# CapBank.net
KiCad netlist of a schematic drawn in Altium Designer
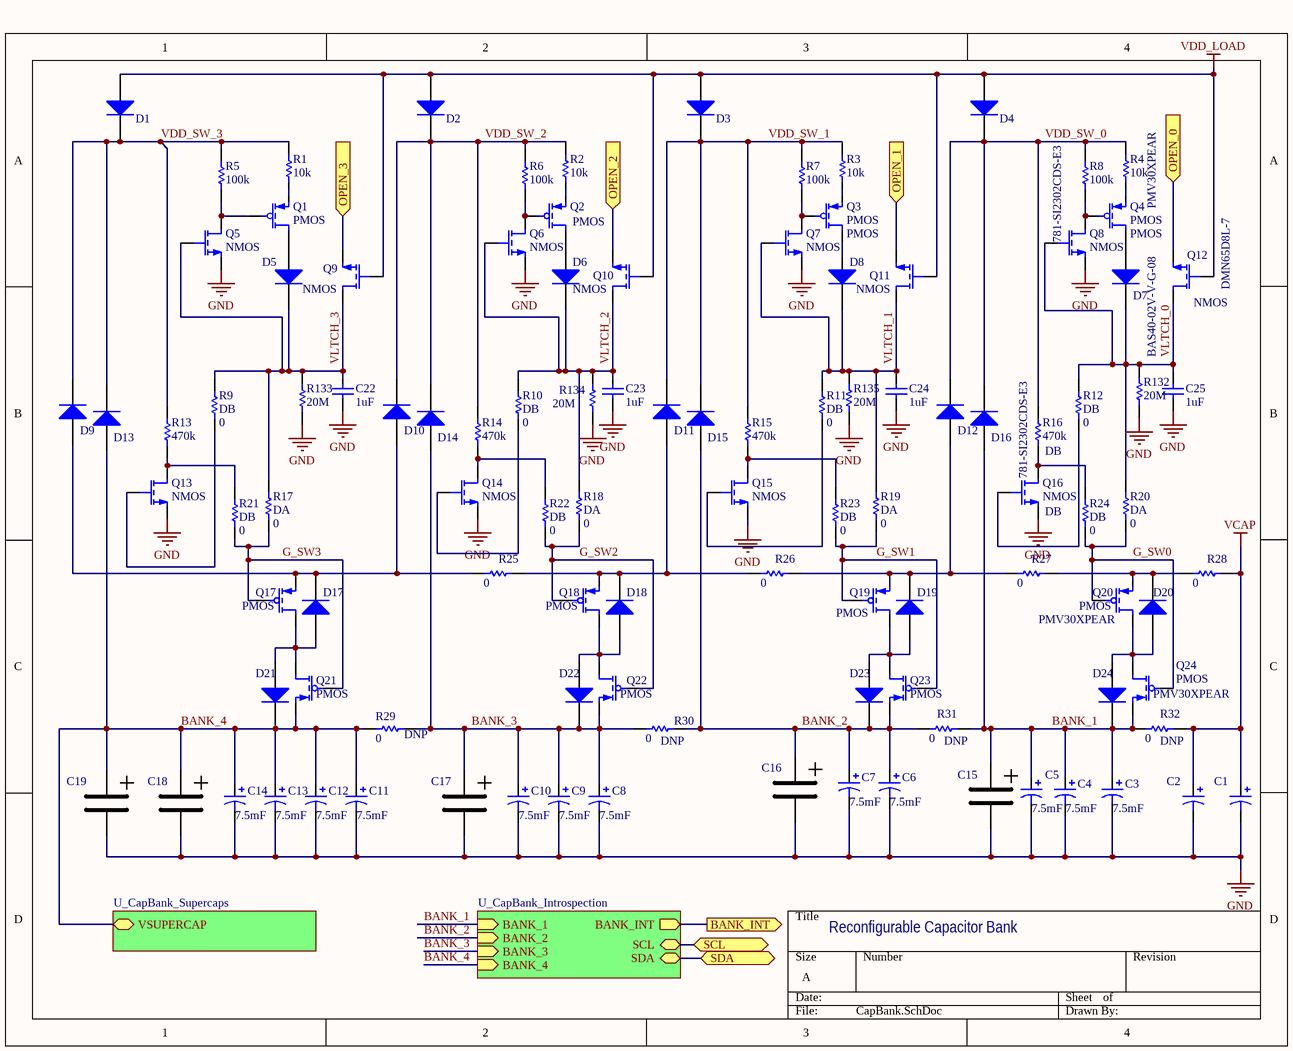
[diagram p0: CapBank.SchDoc]

(export (version "E")
  (design (tool "Eeschema 10.0.6"))
  (components
    (comp (ref "C1")
      (value "Cap - Polarized")
      (footprint "CAP_CPH3225A")
      (description "Polarized Capacitor")
      (fields
        (field (name "DIGI-KEY PART NUMBER") "728-1083-1-ND")
        (field (name "MANUFACTURER PART NUMBER") "CPX3225A752D")
      )
      (libsource (lib "DRP_Basic_2014") (part "Cap - Polarized"))
    )
    (comp (ref "C2")
      (value "Cap - Polarized")
      (footprint "CAP_CPH3225A")
      (description "Polarized Capacitor")
      (fields
        (field (name "DIGI-KEY PART NUMBER") "728-1083-1-ND")
        (field (name "MANUFACTURER PART NUMBER") "CPX3225A752D")
      )
      (libsource (lib "DRP_Basic_2014") (part "Cap - Polarized"))
    )
    (comp (ref "C3")
      (value "7.5mF")
      (footprint "CAP_CPH3225A")
      (description "Polarized Capacitor")
      (fields
        (field (name "DIGI-KEY PART NUMBER") "728-1083-1-ND")
        (field (name "MANUFACTURER PART NUMBER") "CPX3225A752D")
      )
      (libsource (lib "DRP_Basic_2014") (part "Cap - Polarized"))
    )
    (comp (ref "C4")
      (value "7.5mF")
      (footprint "CAP_CPH3225A")
      (description "Polarized Capacitor")
      (fields
        (field (name "DIGI-KEY PART NUMBER") "728-1083-1-ND")
        (field (name "MANUFACTURER PART NUMBER") "CPX3225A752D")
      )
      (libsource (lib "DRP_Basic_2014") (part "Cap - Polarized"))
    )
    (comp (ref "C5")
      (value "7.5mF")
      (footprint "CAP_CPH3225A")
      (description "Polarized Capacitor")
      (fields
        (field (name "DIGI-KEY PART NUMBER") "728-1083-1-ND")
        (field (name "MANUFACTURER PART NUMBER") "CPX3225A752D")
      )
      (libsource (lib "DRP_Basic_2014") (part "Cap - Polarized"))
    )
    (comp (ref "C6")
      (value "7.5mF")
      (footprint "CAP_CPH3225A")
      (description "Polarized Capacitor")
      (fields
        (field (name "DIGI-KEY PART NUMBER") "728-1083-1-ND")
        (field (name "MANUFACTURER PART NUMBER") "CPX3225A752D")
      )
      (libsource (lib "DRP_Basic_2014") (part "Cap - Polarized"))
    )
    (comp (ref "C7")
      (value "7.5mF")
      (footprint "CAP_CPH3225A")
      (description "Polarized Capacitor")
      (fields
        (field (name "DIGI-KEY PART NUMBER") "728-1083-1-ND")
        (field (name "MANUFACTURER PART NUMBER") "CPX3225A752D")
      )
      (libsource (lib "DRP_Basic_2014") (part "Cap - Polarized"))
    )
    (comp (ref "C8")
      (value "7.5mF")
      (footprint "CAP_CPH3225A")
      (description "Polarized Capacitor")
      (fields
        (field (name "DIGI-KEY PART NUMBER") "728-1083-1-ND")
        (field (name "MANUFACTURER PART NUMBER") "CPX3225A752D")
      )
      (libsource (lib "DRP_Basic_2014") (part "Cap - Polarized"))
    )
    (comp (ref "C9")
      (value "7.5mF")
      (footprint "CAP_CPH3225A")
      (description "Polarized Capacitor")
      (fields
        (field (name "DIGI-KEY PART NUMBER") "728-1083-1-ND")
        (field (name "MANUFACTURER PART NUMBER") "CPX3225A752D")
      )
      (libsource (lib "DRP_Basic_2014") (part "Cap - Polarized"))
    )
    (comp (ref "C10")
      (value "7.5mF")
      (footprint "CAP_CPH3225A")
      (description "Polarized Capacitor")
      (fields
        (field (name "DIGI-KEY PART NUMBER") "728-1083-1-ND")
        (field (name "MANUFACTURER PART NUMBER") "CPX3225A752D")
      )
      (libsource (lib "DRP_Basic_2014") (part "Cap - Polarized"))
    )
    (comp (ref "C11")
      (value "7.5mF")
      (footprint "CAP_CPH3225A")
      (description "Polarized Capacitor")
      (fields
        (field (name "DIGI-KEY PART NUMBER") "728-1083-1-ND")
        (field (name "MANUFACTURER PART NUMBER") "CPX3225A752D")
      )
      (libsource (lib "DRP_Basic_2014") (part "Cap - Polarized"))
    )
    (comp (ref "C12")
      (value "7.5mF")
      (footprint "CAP_CPH3225A")
      (description "Polarized Capacitor")
      (fields
        (field (name "DIGI-KEY PART NUMBER") "728-1083-1-ND")
        (field (name "MANUFACTURER PART NUMBER") "CPX3225A752D")
      )
      (libsource (lib "DRP_Basic_2014") (part "Cap - Polarized"))
    )
    (comp (ref "C13")
      (value "7.5mF")
      (footprint "CAP_CPH3225A")
      (description "Polarized Capacitor")
      (fields
        (field (name "DIGI-KEY PART NUMBER") "728-1083-1-ND")
        (field (name "MANUFACTURER PART NUMBER") "CPX3225A752D")
      )
      (libsource (lib "DRP_Basic_2014") (part "Cap - Polarized"))
    )
    (comp (ref "C14")
      (value "7.5mF")
      (footprint "CAP_CPH3225A")
      (description "Polarized Capacitor")
      (fields
        (field (name "DIGI-KEY PART NUMBER") "728-1083-1-ND")
        (field (name "MANUFACTURER PART NUMBER") "CPX3225A752D")
      )
      (libsource (lib "DRP_Basic_2014") (part "Cap - Polarized"))
    )
    (comp (ref "C15")
      (value "304DCN2R7SCBB")
      (footprint "CAP_ILLINOIS_DCN")
      (description "EDLC Supercap")
      (fields
        (field (name "DISTRIBUTOR PART NUMBER") "598-304DCN2R7SCBB")
        (field (name "MANUFACTURER") "Illinois Capacitor / CDE")
      )
      (libsource (lib "Sprite") (part "SUPERCAP"))
    )
    (comp (ref "C16")
      (value "304DCN2R7SCBB")
      (footprint "CAP_ILLINOIS_DCN")
      (description "EDLC Supercap")
      (fields
        (field (name "DISTRIBUTOR PART NUMBER") "598-304DCN2R7SCBB")
        (field (name "MANUFACTURER") "Illinois Capacitor / CDE")
      )
      (libsource (lib "Sprite") (part "SUPERCAP"))
    )
    (comp (ref "C17")
      (value "304DCN2R7SCBB")
      (footprint "CAP_ILLINOIS_DCN")
      (description "EDLC Supercap")
      (fields
        (field (name "DISTRIBUTOR PART NUMBER") "598-304DCN2R7SCBB")
        (field (name "MANUFACTURER") "Illinois Capacitor / CDE")
      )
      (libsource (lib "Sprite") (part "SUPERCAP"))
    )
    (comp (ref "C18")
      (value "304DCN2R7SCBB")
      (footprint "CAP_ILLINOIS_DCN")
      (description "EDLC Supercap")
      (fields
        (field (name "DISTRIBUTOR PART NUMBER") "598-304DCN2R7SCBB")
        (field (name "MANUFACTURER") "Illinois Capacitor / CDE")
      )
      (libsource (lib "Sprite") (part "SUPERCAP"))
    )
    (comp (ref "C19")
      (value "304DCN2R7SCBB")
      (footprint "CAP_ILLINOIS_DCN")
      (description "EDLC Supercap")
      (fields
        (field (name "DISTRIBUTOR PART NUMBER") "598-304DCN2R7SCBB")
        (field (name "MANUFACTURER") "Illinois Capacitor / CDE")
      )
      (libsource (lib "Sprite") (part "SUPERCAP"))
    )
    (comp (ref "C22")
      (value "1uF")
      (footprint "0603")
      (description "Ceramic Capacitor (Surface Mount)")
      (fields
        (field (name "MANUFACTURER") "Murata Electronics North America")
        (field (name "MANUFACTURER PART NUMBER") "GRM188R61A105KA61D")
      )
      (libsource (lib "DRP_Basic_2014") (part "Cap"))
    )
    (comp (ref "C23")
      (value "1uF")
      (footprint "0603")
      (description "Ceramic Capacitor (Surface Mount)")
      (fields
        (field (name "MANUFACTURER") "Murata Electronics North America")
        (field (name "MANUFACTURER PART NUMBER") "GRM188R61A105KA61D")
      )
      (libsource (lib "DRP_Basic_2014") (part "Cap"))
    )
    (comp (ref "C24")
      (value "1uF")
      (footprint "0603")
      (description "Ceramic Capacitor (Surface Mount)")
      (fields
        (field (name "MANUFACTURER") "Murata Electronics North America")
        (field (name "MANUFACTURER PART NUMBER") "GRM188R61A105KA61D")
      )
      (libsource (lib "DRP_Basic_2014") (part "Cap"))
    )
    (comp (ref "C25")
      (value "1uF")
      (footprint "0603")
      (description "Ceramic Capacitor (Surface Mount)")
      (fields
        (field (name "MANUFACTURER") "Murata Electronics North America")
        (field (name "MANUFACTURER PART NUMBER") "GRM188R61A105KA61D")
      )
      (libsource (lib "DRP_Basic_2014") (part "Cap"))
    )
    (comp (ref "D1")
      (value "Diode")
      (footprint "SOD-523")
      (description "General Purpose Diode")
      (fields
        (field (name "MANUFACTURER") "Vishay Semiconductor")
        (field (name "MANUFACTURER PART NUMBER") "BAS40-02V-V-G-08")
      )
      (libsource (lib "DRP_Basic_2014") (part "Diode"))
    )
    (comp (ref "D2")
      (value "Diode")
      (footprint "SOD-523")
      (description "General Purpose Diode")
      (fields
        (field (name "MANUFACTURER") "Vishay Semiconductor")
        (field (name "MANUFACTURER PART NUMBER") "BAS40-02V-V-G-08")
      )
      (libsource (lib "DRP_Basic_2014") (part "Diode"))
    )
    (comp (ref "D3")
      (value "Diode")
      (footprint "SOD-523")
      (description "General Purpose Diode")
      (fields
        (field (name "MANUFACTURER") "Vishay Semiconductor")
        (field (name "MANUFACTURER PART NUMBER") "BAS40-02V-V-G-08")
      )
      (libsource (lib "DRP_Basic_2014") (part "Diode"))
    )
    (comp (ref "D4")
      (value "Diode")
      (footprint "SOD-523")
      (description "General Purpose Diode")
      (fields
        (field (name "MANUFACTURER") "Vishay Semiconductor")
        (field (name "MANUFACTURER PART NUMBER") "BAS40-02V-V-G-08")
      )
      (libsource (lib "DRP_Basic_2014") (part "Diode"))
    )
    (comp (ref "D5")
      (value "Diode")
      (footprint "SOD-523")
      (description "General Purpose Diode")
      (fields
        (field (name "MANUFACTURER") "Vishay Semiconductor")
        (field (name "MANUFACTURER PART NUMBER") "BAS40-02V-V-G-08")
      )
      (libsource (lib "DRP_Basic_2014") (part "Diode"))
    )
    (comp (ref "D6")
      (value "Diode")
      (footprint "SOD-523")
      (description "General Purpose Diode")
      (fields
        (field (name "MANUFACTURER") "Vishay Semiconductor")
        (field (name "MANUFACTURER PART NUMBER") "BAS40-02V-V-G-08")
      )
      (libsource (lib "DRP_Basic_2014") (part "Diode"))
    )
    (comp (ref "D7")
      (value "Diode")
      (footprint "SOD-523")
      (description "General Purpose Diode")
      (fields
        (field (name "MANUFACTURER") "Vishay Semiconductor")
        (field (name "MANUFACTURER PART NUMBER") "BAS40-02V-V-G-08")
        (field (name "DIGI-KEY PART NUMBER") "BAS40-02V-V-G-08GICT-ND")
      )
      (libsource (lib "DRP_Basic_2014") (part "Diode"))
    )
    (comp (ref "D8")
      (value "Diode")
      (footprint "SOD-523")
      (description "General Purpose Diode")
      (fields
        (field (name "MANUFACTURER") "Vishay Semiconductor")
        (field (name "MANUFACTURER PART NUMBER") "BAS40-02V-V-G-08")
      )
      (libsource (lib "") (part "Diode_1"))
    )
    (comp (ref "D9")
      (value "Diode")
      (footprint "SOD-523")
      (description "General Purpose Diode")
      (fields
        (field (name "MANUFACTURER") "Vishay Semiconductor")
        (field (name "MANUFACTURER PART NUMBER") "BAS40-02V-V-G-08")
      )
      (libsource (lib "DRP_Basic_2014") (part "Diode"))
    )
    (comp (ref "D10")
      (value "Diode")
      (footprint "SOD-523")
      (description "General Purpose Diode")
      (fields
        (field (name "MANUFACTURER") "Vishay Semiconductor")
        (field (name "MANUFACTURER PART NUMBER") "BAS40-02V-V-G-08")
      )
      (libsource (lib "DRP_Basic_2014") (part "Diode"))
    )
    (comp (ref "D11")
      (value "Diode")
      (footprint "SOD-523")
      (description "General Purpose Diode")
      (fields
        (field (name "MANUFACTURER") "Vishay Semiconductor")
        (field (name "MANUFACTURER PART NUMBER") "BAS40-02V-V-G-08")
      )
      (libsource (lib "DRP_Basic_2014") (part "Diode"))
    )
    (comp (ref "D12")
      (value "Diode")
      (footprint "SOD-523")
      (description "General Purpose Diode")
      (fields
        (field (name "MANUFACTURER") "Vishay Semiconductor")
        (field (name "MANUFACTURER PART NUMBER") "BAS40-02V-V-G-08")
      )
      (libsource (lib "DRP_Basic_2014") (part "Diode"))
    )
    (comp (ref "D13")
      (value "Diode")
      (footprint "SOD-523")
      (description "General Purpose Diode")
      (fields
        (field (name "MANUFACTURER") "Vishay Semiconductor")
        (field (name "MANUFACTURER PART NUMBER") "BAS40-02V-V-G-08")
      )
      (libsource (lib "DRP_Basic_2014") (part "Diode"))
    )
    (comp (ref "D14")
      (value "Diode")
      (footprint "SOD-523")
      (description "General Purpose Diode")
      (fields
        (field (name "MANUFACTURER") "Vishay Semiconductor")
        (field (name "MANUFACTURER PART NUMBER") "BAS40-02V-V-G-08")
      )
      (libsource (lib "DRP_Basic_2014") (part "Diode"))
    )
    (comp (ref "D15")
      (value "Diode")
      (footprint "SOD-523")
      (description "General Purpose Diode")
      (fields
        (field (name "MANUFACTURER") "Vishay Semiconductor")
        (field (name "MANUFACTURER PART NUMBER") "BAS40-02V-V-G-08")
      )
      (libsource (lib "DRP_Basic_2014") (part "Diode"))
    )
    (comp (ref "D16")
      (value "Diode")
      (footprint "SOD-523")
      (description "General Purpose Diode")
      (fields
        (field (name "MANUFACTURER") "Vishay Semiconductor")
        (field (name "MANUFACTURER PART NUMBER") "BAS40-02V-V-G-08")
      )
      (libsource (lib "DRP_Basic_2014") (part "Diode"))
    )
    (comp (ref "D17")
      (value "Diode")
      (footprint "SOD-523")
      (description "General Purpose Diode")
      (fields
        (field (name "MANUFACTURER") "Vishay Semiconductor")
        (field (name "MANUFACTURER PART NUMBER") "BAS40-02V-V-G-08")
      )
      (libsource (lib "DRP_Basic_2014") (part "Diode"))
    )
    (comp (ref "D18")
      (value "Diode")
      (footprint "SOD-523")
      (description "General Purpose Diode")
      (fields
        (field (name "MANUFACTURER") "Vishay Semiconductor")
        (field (name "MANUFACTURER PART NUMBER") "BAS40-02V-V-G-08")
      )
      (libsource (lib "DRP_Basic_2014") (part "Diode"))
    )
    (comp (ref "D19")
      (value "Diode")
      (footprint "SOD-523")
      (description "General Purpose Diode")
      (fields
        (field (name "MANUFACTURER") "Vishay Semiconductor")
        (field (name "MANUFACTURER PART NUMBER") "BAS40-02V-V-G-08")
      )
      (libsource (lib "DRP_Basic_2014") (part "Diode"))
    )
    (comp (ref "D20")
      (value "Diode")
      (footprint "SOD-523")
      (description "General Purpose Diode")
      (fields
        (field (name "MANUFACTURER") "Vishay Semiconductor")
        (field (name "MANUFACTURER PART NUMBER") "BAS40-02V-V-G-08")
      )
      (libsource (lib "DRP_Basic_2014") (part "Diode"))
    )
    (comp (ref "D21")
      (value "Diode")
      (footprint "SOD-523")
      (description "General Purpose Diode")
      (fields
        (field (name "MANUFACTURER") "Vishay Semiconductor")
        (field (name "MANUFACTURER PART NUMBER") "BAS40-02V-V-G-08")
      )
      (libsource (lib "DRP_Basic_2014") (part "Diode"))
    )
    (comp (ref "D22")
      (value "Diode")
      (footprint "SOD-523")
      (description "General Purpose Diode")
      (fields
        (field (name "MANUFACTURER") "Vishay Semiconductor")
        (field (name "MANUFACTURER PART NUMBER") "BAS40-02V-V-G-08")
      )
      (libsource (lib "DRP_Basic_2014") (part "Diode"))
    )
    (comp (ref "D23")
      (value "Diode")
      (footprint "SOD-523")
      (description "General Purpose Diode")
      (fields
        (field (name "MANUFACTURER") "Vishay Semiconductor")
        (field (name "MANUFACTURER PART NUMBER") "BAS40-02V-V-G-08")
      )
      (libsource (lib "DRP_Basic_2014") (part "Diode"))
    )
    (comp (ref "D24")
      (value "Diode")
      (footprint "SOD-523")
      (description "General Purpose Diode")
      (fields
        (field (name "MANUFACTURER") "Vishay Semiconductor")
        (field (name "MANUFACTURER PART NUMBER") "BAS40-02V-V-G-08")
      )
      (libsource (lib "DRP_Basic_2014") (part "Diode"))
    )
    (comp (ref "Q1")
      (value "PMOS")
      (footprint "SOT23 - N")
      (description "P-Channel MOSFET")
      (fields
        (field (name "DIGI-KEY PART NUMBER") "1727-2531-1-ND")
        (field (name "MANUFACTURER PART NUMBER") "PMV30XPEAR")
      )
      (libsource (lib "DRP_Basic_2014") (part "MOSFET-P"))
    )
    (comp (ref "Q2")
      (value "PMOS")
      (footprint "SOT23 - N")
      (description "P-Channel MOSFET")
      (fields
        (field (name "DIGI-KEY PART NUMBER") "1727-2531-1-ND")
        (field (name "MANUFACTURER PART NUMBER") "PMV30XPEAR")
      )
      (libsource (lib "DRP_Basic_2014") (part "MOSFET-P"))
    )
    (comp (ref "Q3")
      (value "PMOS")
      (footprint "SOT23 - N")
      (description "P-Channel MOSFET")
      (fields
        (field (name "DIGI-KEY PART NUMBER") "1727-2531-1-ND")
        (field (name "MANUFACTURER PART NUMBER") "PMV30XPEAR")
        (field (name "ALTIUM_VALUE") "PMOS")
      )
      (libsource (lib "DRP_Basic_2014") (part "MOSFET-P"))
    )
    (comp (ref "Q4")
      (value "PMOS")
      (footprint "SOT23 - N")
      (description "P-Channel MOSFET")
      (fields
        (field (name "DIGI-KEY PART NUMBER") "1727-2531-1-ND")
        (field (name "MANUFACTURER PART NUMBER") "PMV30XPEAR")
        (field (name "MANUFACTURER") "Nexperia")
        (field (name "ALTIUM_VALUE") "PMOS")
      )
      (libsource (lib "DRP_Basic_2014") (part "MOSFET-P"))
    )
    (comp (ref "Q5")
      (value "NMOS")
      (footprint "SOT23 - N")
      (description "N-Channel MOSFET")
      (fields
        (field (name "DIGI-KEY PART NUMBER") "SI2302CDS-T1-E3CT-ND")
        (field (name "MANUFACTURER PART NUMBER") "SI2302CDS-T1-E3")
      )
      (libsource (lib "DRP_Basic_2014") (part "MOSFET-N"))
    )
    (comp (ref "Q6")
      (value "NMOS")
      (footprint "SOT23 - N")
      (description "N-Channel MOSFET")
      (fields
        (field (name "DIGI-KEY PART NUMBER") "SI2302CDS-T1-E3CT-ND")
        (field (name "MANUFACTURER PART NUMBER") "SI2302CDS-T1-E3")
      )
      (libsource (lib "DRP_Basic_2014") (part "MOSFET-N"))
    )
    (comp (ref "Q7")
      (value "NMOS")
      (footprint "SOT23 - N")
      (description "N-Channel MOSFET")
      (fields
        (field (name "DIGI-KEY PART NUMBER") "SI2302CDS-T1-E3CT-ND")
        (field (name "MANUFACTURER PART NUMBER") "SI2302CDS-T1-E3")
      )
      (libsource (lib "DRP_Basic_2014") (part "MOSFET-N"))
    )
    (comp (ref "Q8")
      (value "NMOS")
      (footprint "SOT23 - N")
      (description "N-Channel MOSFET")
      (fields
        (field (name "DIGI-KEY PART NUMBER") "SI2302CDS-T1-E3CT-ND")
        (field (name "MANUFACTURER PART NUMBER") "SI2302CDS-T1-E3")
        (field (name "MOUSER PART NUMBER") "781-SI2302CDS-E3")
      )
      (libsource (lib "DRP_Basic_2014") (part "MOSFET-N"))
    )
    (comp (ref "Q9")
      (value "NMOS")
      (footprint "SOT23 - N")
      (description "N-Channel MOSFET")
      (fields
        (field (name "DIGI-KEY PART NUMBER") "DMN65D8L-7DICT-ND")
        (field (name "MANUFACTURER PART NUMBER") "DMN65D8L-7")
      )
      (libsource (lib "DRP_Basic_2014") (part "MOSFET-N"))
    )
    (comp (ref "Q10")
      (value "NMOS")
      (footprint "SOT23 - N")
      (description "N-Channel MOSFET")
      (fields
        (field (name "DIGI-KEY PART NUMBER") "DMN65D8L-7DICT-ND")
        (field (name "MANUFACTURER PART NUMBER") "DMN65D8L-7")
      )
      (libsource (lib "DRP_Basic_2014") (part "MOSFET-N"))
    )
    (comp (ref "Q11")
      (value "NMOS")
      (footprint "SOT23 - N")
      (description "N-Channel MOSFET")
      (fields
        (field (name "DIGI-KEY PART NUMBER") "DMN65D8L-7DICT-ND")
        (field (name "MANUFACTURER PART NUMBER") "DMN65D8L-7")
      )
      (libsource (lib "DRP_Basic_2014") (part "MOSFET-N"))
    )
    (comp (ref "Q12")
      (value "NMOS")
      (footprint "SOT23 - N")
      (description "N-Channel MOSFET")
      (fields
        (field (name "DIGI-KEY PART NUMBER") "DMN65D8L-7DICT-ND")
        (field (name "MANUFACTURER PART NUMBER") "DMN65D8L-7")
        (field (name "MANUFACTURER") "Diodes Incorporated")
      )
      (libsource (lib "DRP_Basic_2014") (part "MOSFET-N"))
    )
    (comp (ref "Q13")
      (value "NMOS")
      (footprint "SOT23 - N")
      (description "N-Channel MOSFET")
      (fields
        (field (name "DIGI-KEY PART NUMBER") "SI2302CDS-T1-E3CT-ND")
        (field (name "MANUFACTURER PART NUMBER") "SI2302CDS-T1-E3")
      )
      (libsource (lib "DRP_Basic_2014") (part "MOSFET-N"))
    )
    (comp (ref "Q14")
      (value "NMOS")
      (footprint "SOT23 - N")
      (description "N-Channel MOSFET")
      (fields
        (field (name "DIGI-KEY PART NUMBER") "SI2302CDS-T1-E3CT-ND")
        (field (name "MANUFACTURER PART NUMBER") "SI2302CDS-T1-E3")
      )
      (libsource (lib "DRP_Basic_2014") (part "MOSFET-N"))
    )
    (comp (ref "Q15")
      (value "NMOS")
      (footprint "SOT23 - N")
      (description "N-Channel MOSFET")
      (fields
        (field (name "DIGI-KEY PART NUMBER") "SI2302CDS-T1-E3CT-ND")
        (field (name "MANUFACTURER PART NUMBER") "SI2302CDS-T1-E3")
      )
      (libsource (lib "DRP_Basic_2014") (part "MOSFET-N"))
    )
    (comp (ref "Q16")
      (value "NMOS")
      (footprint "SOT23 - N")
      (description "N-Channel MOSFET")
      (fields
        (field (name "DIGI-KEY PART NUMBER") "SI2302CDS-T1-E3CT-ND")
        (field (name "MANUFACTURER PART NUMBER") "SI2302CDS-T1-E3")
        (field (name "NOTE") "DB")
        (field (name "MOUSER PART NUMBER") "781-SI2302CDS-E3")
      )
      (libsource (lib "DRP_Basic_2014") (part "MOSFET-N"))
    )
    (comp (ref "Q17")
      (value "PMOS")
      (footprint "SOT23 - N")
      (description "P-Channel MOSFET")
      (fields
        (field (name "DIGI-KEY PART NUMBER") "1727-2531-1-ND")
        (field (name "MANUFACTURER PART NUMBER") "PMV30XPEAR")
      )
      (libsource (lib "DRP_Basic_2014") (part "MOSFET-P"))
    )
    (comp (ref "Q18")
      (value "PMOS")
      (footprint "SOT23 - N")
      (description "P-Channel MOSFET")
      (fields
        (field (name "DIGI-KEY PART NUMBER") "1727-2531-1-ND")
        (field (name "MANUFACTURER PART NUMBER") "PMV30XPEAR")
      )
      (libsource (lib "DRP_Basic_2014") (part "MOSFET-P"))
    )
    (comp (ref "Q19")
      (value "PMOS")
      (footprint "SOT23 - N")
      (description "P-Channel MOSFET")
      (fields
        (field (name "DIGI-KEY PART NUMBER") "1727-2531-1-ND")
        (field (name "MANUFACTURER PART NUMBER") "PMV30XPEAR")
      )
      (libsource (lib "DRP_Basic_2014") (part "MOSFET-P"))
    )
    (comp (ref "Q20")
      (value "PMOS")
      (footprint "SOT23 - N")
      (description "P-Channel MOSFET")
      (fields
        (field (name "DIGI-KEY PART NUMBER") "1727-2531-1-ND")
        (field (name "MANUFACTURER PART NUMBER") "PMV30XPEAR")
        (field (name "MANUFACTURER") "Nexperia")
      )
      (libsource (lib "DRP_Basic_2014") (part "MOSFET-P"))
    )
    (comp (ref "Q21")
      (value "PMOS")
      (footprint "SOT23 - N")
      (description "P-Channel MOSFET")
      (fields
        (field (name "DIGI-KEY PART NUMBER") "1727-2531-1-ND")
        (field (name "MANUFACTURER PART NUMBER") "PMV30XPEAR")
      )
      (libsource (lib "DRP_Basic_2014") (part "MOSFET-P"))
    )
    (comp (ref "Q22")
      (value "PMOS")
      (footprint "SOT23 - N")
      (description "P-Channel MOSFET")
      (fields
        (field (name "DIGI-KEY PART NUMBER") "1727-2531-1-ND")
        (field (name "MANUFACTURER PART NUMBER") "PMV30XPEAR")
      )
      (libsource (lib "DRP_Basic_2014") (part "MOSFET-P"))
    )
    (comp (ref "Q23")
      (value "PMOS")
      (footprint "SOT23 - N")
      (description "P-Channel MOSFET")
      (fields
        (field (name "DIGI-KEY PART NUMBER") "1727-2531-1-ND")
        (field (name "MANUFACTURER PART NUMBER") "PMV30XPEAR")
      )
      (libsource (lib "DRP_Basic_2014") (part "MOSFET-P"))
    )
    (comp (ref "Q24")
      (value "PMOS")
      (footprint "SOT23 - N")
      (description "P-Channel MOSFET")
      (fields
        (field (name "DIGI-KEY PART NUMBER") "1727-2531-1-ND")
        (field (name "MANUFACTURER PART NUMBER") "PMV30XPEAR")
        (field (name "MANUFACTURER") "Nexperia")
      )
      (libsource (lib "DRP_Basic_2014") (part "MOSFET-P"))
    )
    (comp (ref "R1")
      (value "10k")
      (footprint "0603")
      (description "Chip Resistor (Surface Mount)")
      (fields
        (field (name "MANUFACTURER") "Yageo")
        (field (name "MANUFACTURER PART NUMBER") "RT0603DRD0747KL")
      )
      (libsource (lib "DRP_Basic_2014") (part "Res"))
    )
    (comp (ref "R2")
      (value "10k")
      (footprint "0603")
      (description "Chip Resistor (Surface Mount)")
      (fields
        (field (name "MANUFACTURER") "Yageo")
        (field (name "MANUFACTURER PART NUMBER") "RT0603DRD0747KL")
      )
      (libsource (lib "DRP_Basic_2014") (part "Res"))
    )
    (comp (ref "R3")
      (value "10k")
      (footprint "0603")
      (description "Chip Resistor (Surface Mount)")
      (fields
        (field (name "MANUFACTURER") "Yageo")
        (field (name "MANUFACTURER PART NUMBER") "RT0603DRD0747KL")
      )
      (libsource (lib "DRP_Basic_2014") (part "Res"))
    )
    (comp (ref "R4")
      (value "10k")
      (footprint "0603")
      (description "Chip Resistor (Surface Mount)")
      (fields
        (field (name "MANUFACTURER") "Yageo")
        (field (name "MANUFACTURER PART NUMBER") "RT0603DRD0747KL")
      )
      (libsource (lib "DRP_Basic_2014") (part "Res"))
    )
    (comp (ref "R5")
      (value "100k")
      (footprint "0603")
      (description "Chip Resistor (Surface Mount)")
      (fields
        (field (name "MANUFACTURER") "Yageo")
        (field (name "MANUFACTURER PART NUMBER") "RC0603FR-071ML")
      )
      (libsource (lib "DRP_Basic_2014") (part "Res"))
    )
    (comp (ref "R6")
      (value "100k")
      (footprint "0603")
      (description "Chip Resistor (Surface Mount)")
      (fields
        (field (name "MANUFACTURER") "Yageo")
        (field (name "MANUFACTURER PART NUMBER") "RC0603FR-071ML")
      )
      (libsource (lib "DRP_Basic_2014") (part "Res"))
    )
    (comp (ref "R7")
      (value "100k")
      (footprint "0603")
      (description "Chip Resistor (Surface Mount)")
      (fields
        (field (name "MANUFACTURER") "Yageo")
        (field (name "MANUFACTURER PART NUMBER") "RC0603FR-071ML")
      )
      (libsource (lib "DRP_Basic_2014") (part "Res"))
    )
    (comp (ref "R8")
      (value "100k")
      (footprint "0603")
      (description "Chip Resistor (Surface Mount)")
      (fields
        (field (name "MANUFACTURER") "Yageo")
        (field (name "MANUFACTURER PART NUMBER") "RC0603FR-071ML")
      )
      (libsource (lib "DRP_Basic_2014") (part "Res"))
    )
    (comp (ref "R9")
      (value "DB")
      (footprint "0603")
      (description "Chip Resistor (Surface Mount)")
      (fields
        (field (name "MANUFACTURER") "Yageo")
        (field (name "MANUFACTURER PART NUMBER") "RC0603JR-070RL")
        (field (name "ALTIUM_VALUE") "0")
      )
      (libsource (lib "DRP_Basic_2014") (part "Res"))
    )
    (comp (ref "R10")
      (value "DB")
      (footprint "0603")
      (description "Chip Resistor (Surface Mount)")
      (fields
        (field (name "MANUFACTURER") "Yageo")
        (field (name "MANUFACTURER PART NUMBER") "RC0603JR-070RL")
        (field (name "ALTIUM_VALUE") "0")
      )
      (libsource (lib "DRP_Basic_2014") (part "Res"))
    )
    (comp (ref "R11")
      (value "DB")
      (footprint "0603")
      (description "Chip Resistor (Surface Mount)")
      (fields
        (field (name "MANUFACTURER") "Yageo")
        (field (name "MANUFACTURER PART NUMBER") "RC0603JR-070RL")
        (field (name "ALTIUM_VALUE") "0")
      )
      (libsource (lib "DRP_Basic_2014") (part "Res"))
    )
    (comp (ref "R12")
      (value "DB")
      (footprint "0603")
      (description "Chip Resistor (Surface Mount)")
      (fields
        (field (name "MANUFACTURER") "Yageo")
        (field (name "MANUFACTURER PART NUMBER") "RC0603JR-070RL")
        (field (name "ALTIUM_VALUE") "0")
      )
      (libsource (lib "DRP_Basic_2014") (part "Res"))
    )
    (comp (ref "R13")
      (value "470k")
      (footprint "0603")
      (description "Chip Resistor (Surface Mount)")
      (fields
        (field (name "MANUFACTURER") "Yageo")
        (field (name "MANUFACTURER PART NUMBER") "RC0603FR-07470KL")
      )
      (libsource (lib "DRP_Basic_2014") (part "Res"))
    )
    (comp (ref "R14")
      (value "470k")
      (footprint "0603")
      (description "Chip Resistor (Surface Mount)")
      (fields
        (field (name "MANUFACTURER") "Yageo")
        (field (name "MANUFACTURER PART NUMBER") "RC0603FR-07470KL")
      )
      (libsource (lib "DRP_Basic_2014") (part "Res"))
    )
    (comp (ref "R15")
      (value "470k")
      (footprint "0603")
      (description "Chip Resistor (Surface Mount)")
      (fields
        (field (name "MANUFACTURER") "Yageo")
        (field (name "MANUFACTURER PART NUMBER") "RC0603FR-07470KL")
      )
      (libsource (lib "DRP_Basic_2014") (part "Res"))
    )
    (comp (ref "R16")
      (value "470k")
      (footprint "0603")
      (description "Chip Resistor (Surface Mount)")
      (fields
        (field (name "MANUFACTURER") "Yageo")
        (field (name "MANUFACTURER PART NUMBER") "RC0603FR-07470KL")
        (field (name "NOTE") "DB")
      )
      (libsource (lib "DRP_Basic_2014") (part "Res"))
    )
    (comp (ref "R17")
      (value "DA")
      (footprint "0603")
      (description "Chip Resistor (Surface Mount)")
      (fields
        (field (name "MANUFACTURER") "Yageo")
        (field (name "MANUFACTURER PART NUMBER") "RC0603JR-070RL")
        (field (name "ALTIUM_VALUE") "0")
      )
      (libsource (lib "DRP_Basic_2014") (part "Res"))
    )
    (comp (ref "R18")
      (value "DA")
      (footprint "0603")
      (description "Chip Resistor (Surface Mount)")
      (fields
        (field (name "MANUFACTURER") "Yageo")
        (field (name "MANUFACTURER PART NUMBER") "RC0603JR-070RL")
        (field (name "ALTIUM_VALUE") "0")
      )
      (libsource (lib "DRP_Basic_2014") (part "Res"))
    )
    (comp (ref "R19")
      (value "DA")
      (footprint "0603")
      (description "Chip Resistor (Surface Mount)")
      (fields
        (field (name "MANUFACTURER") "Yageo")
        (field (name "MANUFACTURER PART NUMBER") "RC0603JR-070RL")
        (field (name "ALTIUM_VALUE") "0")
      )
      (libsource (lib "DRP_Basic_2014") (part "Res"))
    )
    (comp (ref "R20")
      (value "DA")
      (footprint "0603")
      (description "Chip Resistor (Surface Mount)")
      (fields
        (field (name "MANUFACTURER") "Yageo")
        (field (name "MANUFACTURER PART NUMBER") "RC0603JR-070RL")
        (field (name "ALTIUM_VALUE") "0")
      )
      (libsource (lib "DRP_Basic_2014") (part "Res"))
    )
    (comp (ref "R21")
      (value "DB")
      (footprint "0603")
      (description "Chip Resistor (Surface Mount)")
      (fields
        (field (name "MANUFACTURER") "Yageo")
        (field (name "MANUFACTURER PART NUMBER") "RC0603JR-070RL")
        (field (name "ALTIUM_VALUE") "0")
      )
      (libsource (lib "DRP_Basic_2014") (part "Res"))
    )
    (comp (ref "R22")
      (value "DB")
      (footprint "0603")
      (description "Chip Resistor (Surface Mount)")
      (fields
        (field (name "MANUFACTURER") "Yageo")
        (field (name "MANUFACTURER PART NUMBER") "RC0603JR-070RL")
        (field (name "ALTIUM_VALUE") "0")
      )
      (libsource (lib "DRP_Basic_2014") (part "Res"))
    )
    (comp (ref "R23")
      (value "DB")
      (footprint "0603")
      (description "Chip Resistor (Surface Mount)")
      (fields
        (field (name "MANUFACTURER") "Yageo")
        (field (name "MANUFACTURER PART NUMBER") "RC0603JR-070RL")
        (field (name "ALTIUM_VALUE") "0")
      )
      (libsource (lib "DRP_Basic_2014") (part "Res"))
    )
    (comp (ref "R24")
      (value "DB")
      (footprint "0603")
      (description "Chip Resistor (Surface Mount)")
      (fields
        (field (name "MANUFACTURER") "Yageo")
        (field (name "MANUFACTURER PART NUMBER") "RC0603JR-070RL")
        (field (name "ALTIUM_VALUE") "0")
      )
      (libsource (lib "DRP_Basic_2014") (part "Res"))
    )
    (comp (ref "R25")
      (value "0")
      (footprint "0603")
      (description "Chip Resistor (Surface Mount)")
      (fields
        (field (name "MANUFACTURER") "Yageo")
        (field (name "MANUFACTURER PART NUMBER") "RC0603JR-070RL")
      )
      (libsource (lib "DRP_Basic_2014") (part "Res"))
    )
    (comp (ref "R26")
      (value "0")
      (footprint "0603")
      (description "Chip Resistor (Surface Mount)")
      (fields
        (field (name "MANUFACTURER") "Yageo")
        (field (name "MANUFACTURER PART NUMBER") "RC0603JR-070RL")
      )
      (libsource (lib "DRP_Basic_2014") (part "Res"))
    )
    (comp (ref "R27")
      (value "0")
      (footprint "0603")
      (description "Chip Resistor (Surface Mount)")
      (fields
        (field (name "MANUFACTURER") "Yageo")
        (field (name "MANUFACTURER PART NUMBER") "RC0603JR-070RL")
      )
      (libsource (lib "DRP_Basic_2014") (part "Res"))
    )
    (comp (ref "R28")
      (value "0")
      (footprint "0603")
      (description "Chip Resistor (Surface Mount)")
      (fields
        (field (name "MANUFACTURER") "Yageo")
        (field (name "MANUFACTURER PART NUMBER") "RC0603JR-070RL")
      )
      (libsource (lib "DRP_Basic_2014") (part "Res"))
    )
    (comp (ref "R29")
      (value "0")
      (footprint "0603")
      (description "Chip Resistor (Surface Mount)")
      (fields
        (field (name "MANUFACTURER") "Yageo")
        (field (name "MANUFACTURER PART NUMBER") "RC0603JR-070RL")
        (field (name "NOTE") "DNP")
      )
      (libsource (lib "DRP_Basic_2014") (part "Res"))
    )
    (comp (ref "R30")
      (value "0")
      (footprint "0603")
      (description "Chip Resistor (Surface Mount)")
      (fields
        (field (name "MANUFACTURER") "Yageo")
        (field (name "MANUFACTURER PART NUMBER") "RC0603JR-070RL")
        (field (name "NOTE") "DNP")
      )
      (libsource (lib "DRP_Basic_2014") (part "Res"))
    )
    (comp (ref "R31")
      (value "0")
      (footprint "0603")
      (description "Chip Resistor (Surface Mount)")
      (fields
        (field (name "MANUFACTURER") "Yageo")
        (field (name "MANUFACTURER PART NUMBER") "RC0603JR-070RL")
        (field (name "NOTE") "DNP")
      )
      (libsource (lib "DRP_Basic_2014") (part "Res"))
    )
    (comp (ref "R32")
      (value "0")
      (footprint "0603")
      (description "Chip Resistor (Surface Mount)")
      (fields
        (field (name "MANUFACTURER") "Yageo")
        (field (name "MANUFACTURER PART NUMBER") "RC0603JR-070RL")
        (field (name "NOTE") "DNP")
      )
      (libsource (lib "DRP_Basic_2014") (part "Res"))
    )
    (comp (ref "R132")
      (value "20M")
      (footprint "0603")
      (description "Chip Resistor (Surface Mount)")
      (fields (field (name "MANUFACTURER") "Generic Chip Res (TBD)") (field (name "Comment") "Res"))
      (libsource (lib "DRP_Basic_2014") (part "Res"))
    )
    (comp (ref "R133")
      (value "20M")
      (footprint "0603")
      (description "Chip Resistor (Surface Mount)")
      (fields (field (name "MANUFACTURER") "Generic Chip Res (TBD)") (field (name "Comment") "Res"))
      (libsource (lib "DRP_Basic_2014") (part "Res"))
    )
    (comp (ref "R134")
      (value "20M")
      (footprint "0603")
      (description "Chip Resistor (Surface Mount)")
      (fields (field (name "MANUFACTURER") "Generic Chip Res (TBD)") (field (name "Comment") "Res"))
      (libsource (lib "DRP_Basic_2014") (part "Res"))
    )
    (comp (ref "R135")
      (value "20M")
      (footprint "0603")
      (description "Chip Resistor (Surface Mount)")
      (fields (field (name "MANUFACTURER") "Generic Chip Res (TBD)") (field (name "Comment") "Res"))
      (libsource (lib "DRP_Basic_2014") (part "Res"))
    )
  )
  (nets
    (net (code "1") (name "/BANK_1") (class "Default")
      (node (ref "C15") (pin "1") (pinfunction "P_1") (pintype "passive"))
      (node (ref "C3") (pin "1") (pinfunction "1_1") (pintype "passive"))
      (node (ref "C4") (pin "1") (pinfunction "1_1") (pintype "passive"))
      (node (ref "C5") (pin "1") (pinfunction "1_1") (pintype "passive"))
      (node (ref "D16") (pin "1") (pinfunction "A_1") (pintype "passive"))
      (node (ref "D24") (pin "2") (pinfunction "C_2") (pintype "passive"))
      (node (ref "Q24") (pin "2") (pinfunction "S_2") (pintype "passive"))
      (node (ref "R31") (pin "2") (pinfunction "2_2") (pintype "passive"))
      (node (ref "R32") (pin "1") (pinfunction "1_1") (pintype "passive"))
    )
    (net (code "2") (name "/BANK_2") (class "Default")
      (node (ref "C16") (pin "1") (pinfunction "P_1") (pintype "passive"))
      (node (ref "C6") (pin "1") (pinfunction "1_1") (pintype "passive"))
      (node (ref "C7") (pin "1") (pinfunction "1_1") (pintype "passive"))
      (node (ref "D15") (pin "1") (pinfunction "A_1") (pintype "passive"))
      (node (ref "D23") (pin "2") (pinfunction "C_2") (pintype "passive"))
      (node (ref "Q23") (pin "2") (pinfunction "S_2") (pintype "passive"))
      (node (ref "R30") (pin "2") (pinfunction "2_2") (pintype "passive"))
      (node (ref "R31") (pin "1") (pinfunction "1_1") (pintype "passive"))
    )
    (net (code "3") (name "/BANK_3") (class "Default")
      (node (ref "C10") (pin "1") (pinfunction "1_1") (pintype "passive"))
      (node (ref "C17") (pin "1") (pinfunction "P_1") (pintype "passive"))
      (node (ref "C8") (pin "1") (pinfunction "1_1") (pintype "passive"))
      (node (ref "C9") (pin "1") (pinfunction "1_1") (pintype "passive"))
      (node (ref "D14") (pin "1") (pinfunction "A_1") (pintype "passive"))
      (node (ref "D22") (pin "2") (pinfunction "C_2") (pintype "passive"))
      (node (ref "Q22") (pin "2") (pinfunction "S_2") (pintype "passive"))
      (node (ref "R29") (pin "2") (pinfunction "2_2") (pintype "passive"))
      (node (ref "R30") (pin "1") (pinfunction "1_1") (pintype "passive"))
    )
    (net (code "4") (name "/BANK_4") (class "Default")
      (node (ref "C11") (pin "1") (pinfunction "1_1") (pintype "passive"))
      (node (ref "C12") (pin "1") (pinfunction "1_1") (pintype "passive"))
      (node (ref "C13") (pin "1") (pinfunction "1_1") (pintype "passive"))
      (node (ref "C14") (pin "1") (pinfunction "1_1") (pintype "passive"))
      (node (ref "C18") (pin "1") (pinfunction "P_1") (pintype "passive"))
      (node (ref "C19") (pin "1") (pinfunction "P_1") (pintype "passive"))
      (node (ref "D13") (pin "1") (pinfunction "A_1") (pintype "passive"))
      (node (ref "D21") (pin "2") (pinfunction "C_2") (pintype "passive"))
      (node (ref "Q21") (pin "2") (pinfunction "S_2") (pintype "passive"))
      (node (ref "R29") (pin "1") (pinfunction "1_1") (pintype "passive"))
    )
    (net (code "6") (name "/G_SW0") (class "Default")
      (node (ref "Q20") (pin "1") (pinfunction "G_1") (pintype "passive"))
      (node (ref "Q24") (pin "1") (pinfunction "G_1") (pintype "passive"))
      (node (ref "R20") (pin "1") (pinfunction "1_1") (pintype "passive"))
      (node (ref "R24") (pin "1") (pinfunction "1_1") (pintype "passive"))
    )
    (net (code "7") (name "/G_SW1") (class "Default")
      (node (ref "Q19") (pin "1") (pinfunction "G_1") (pintype "passive"))
      (node (ref "Q23") (pin "1") (pinfunction "G_1") (pintype "passive"))
      (node (ref "R19") (pin "1") (pinfunction "1_1") (pintype "passive"))
      (node (ref "R23") (pin "1") (pinfunction "1_1") (pintype "passive"))
    )
    (net (code "8") (name "/G_SW2") (class "Default")
      (node (ref "Q18") (pin "1") (pinfunction "G_1") (pintype "passive"))
      (node (ref "Q22") (pin "1") (pinfunction "G_1") (pintype "passive"))
      (node (ref "R18") (pin "1") (pinfunction "1_1") (pintype "passive"))
      (node (ref "R22") (pin "1") (pinfunction "1_1") (pintype "passive"))
    )
    (net (code "9") (name "/G_SW3") (class "Default")
      (node (ref "Q17") (pin "1") (pinfunction "G_1") (pintype "passive"))
      (node (ref "Q21") (pin "1") (pinfunction "G_1") (pintype "passive"))
      (node (ref "R17") (pin "1") (pinfunction "1_1") (pintype "passive"))
      (node (ref "R21") (pin "1") (pinfunction "1_1") (pintype "passive"))
    )
    (net (code "10") (name "/OPEN_0") (class "Default")
      (node (ref "Q12") (pin "2") (pinfunction "S_2") (pintype "passive"))
    )
    (net (code "11") (name "/OPEN_1") (class "Default")
      (node (ref "Q11") (pin "2") (pinfunction "S_2") (pintype "passive"))
    )
    (net (code "12") (name "/OPEN_2") (class "Default")
      (node (ref "Q10") (pin "2") (pinfunction "S_2") (pintype "passive"))
    )
    (net (code "13") (name "/OPEN_3") (class "Default")
      (node (ref "Q9") (pin "2") (pinfunction "S_2") (pintype "passive"))
    )
    (net (code "16") (name "/VDD_SW_0") (class "Default")
      (node (ref "D12") (pin "2") (pinfunction "C_2") (pintype "passive"))
      (node (ref "D16") (pin "2") (pinfunction "C_2") (pintype "passive"))
      (node (ref "D4") (pin "2") (pinfunction "C_2") (pintype "passive"))
      (node (ref "R16") (pin "2") (pinfunction "2_2") (pintype "passive"))
      (node (ref "R4") (pin "2") (pinfunction "2_2") (pintype "passive"))
      (node (ref "R8") (pin "2") (pinfunction "2_2") (pintype "passive"))
    )
    (net (code "17") (name "/VDD_SW_1") (class "Default")
      (node (ref "D11") (pin "2") (pinfunction "C_2") (pintype "passive"))
      (node (ref "D15") (pin "2") (pinfunction "C_2") (pintype "passive"))
      (node (ref "D3") (pin "2") (pinfunction "C_2") (pintype "passive"))
      (node (ref "R15") (pin "2") (pinfunction "2_2") (pintype "passive"))
      (node (ref "R3") (pin "2") (pinfunction "2_2") (pintype "passive"))
      (node (ref "R7") (pin "2") (pinfunction "2_2") (pintype "passive"))
    )
    (net (code "18") (name "/VDD_SW_2") (class "Default")
      (node (ref "D10") (pin "2") (pinfunction "C_2") (pintype "passive"))
      (node (ref "D14") (pin "2") (pinfunction "C_2") (pintype "passive"))
      (node (ref "D2") (pin "2") (pinfunction "C_2") (pintype "passive"))
      (node (ref "R14") (pin "2") (pinfunction "2_2") (pintype "passive"))
      (node (ref "R2") (pin "2") (pinfunction "2_2") (pintype "passive"))
      (node (ref "R6") (pin "2") (pinfunction "2_2") (pintype "passive"))
    )
    (net (code "19") (name "/VDD_SW_3") (class "Default")
      (node (ref "D1") (pin "2") (pinfunction "C_2") (pintype "passive"))
      (node (ref "D13") (pin "2") (pinfunction "C_2") (pintype "passive"))
      (node (ref "D9") (pin "2") (pinfunction "C_2") (pintype "passive"))
      (node (ref "R1") (pin "2") (pinfunction "2_2") (pintype "passive"))
      (node (ref "R13") (pin "2") (pinfunction "2_2") (pintype "passive"))
      (node (ref "R5") (pin "2") (pinfunction "2_2") (pintype "passive"))
    )
    (net (code "20") (name "/VLTCH_0") (class "Default")
      (node (ref "C25") (pin "2") (pinfunction "2_2") (pintype "passive"))
      (node (ref "D7") (pin "2") (pinfunction "C_2") (pintype "passive"))
      (node (ref "Q12") (pin "3") (pinfunction "D_3") (pintype "passive"))
      (node (ref "Q8") (pin "1") (pinfunction "G_1") (pintype "passive"))
      (node (ref "R12") (pin "2") (pinfunction "2_2") (pintype "passive"))
      (node (ref "R132") (pin "2") (pinfunction "2_2") (pintype "passive"))
      (node (ref "R20") (pin "2") (pinfunction "2_2") (pintype "passive"))
    )
    (net (code "21") (name "/VLTCH_1") (class "Default")
      (node (ref "C24") (pin "2") (pinfunction "2_2") (pintype "passive"))
      (node (ref "D8") (pin "2") (pinfunction "C_2") (pintype "passive"))
      (node (ref "Q11") (pin "3") (pinfunction "D_3") (pintype "passive"))
      (node (ref "Q7") (pin "1") (pinfunction "G_1") (pintype "passive"))
      (node (ref "R11") (pin "2") (pinfunction "2_2") (pintype "passive"))
      (node (ref "R135") (pin "2") (pinfunction "2_2") (pintype "passive"))
      (node (ref "R19") (pin "2") (pinfunction "2_2") (pintype "passive"))
    )
    (net (code "22") (name "/VLTCH_2") (class "Default")
      (node (ref "C23") (pin "2") (pinfunction "2_2") (pintype "passive"))
      (node (ref "D6") (pin "2") (pinfunction "C_2") (pintype "passive"))
      (node (ref "Q10") (pin "3") (pinfunction "D_3") (pintype "passive"))
      (node (ref "Q6") (pin "1") (pinfunction "G_1") (pintype "passive"))
      (node (ref "R10") (pin "2") (pinfunction "2_2") (pintype "passive"))
      (node (ref "R134") (pin "2") (pinfunction "2_2") (pintype "passive"))
      (node (ref "R18") (pin "2") (pinfunction "2_2") (pintype "passive"))
    )
    (net (code "23") (name "/VLTCH_3") (class "Default")
      (node (ref "C22") (pin "2") (pinfunction "2_2") (pintype "passive"))
      (node (ref "D5") (pin "2") (pinfunction "C_2") (pintype "passive"))
      (node (ref "Q5") (pin "1") (pinfunction "G_1") (pintype "passive"))
      (node (ref "Q9") (pin "3") (pinfunction "D_3") (pintype "passive"))
      (node (ref "R133") (pin "2") (pinfunction "2_2") (pintype "passive"))
      (node (ref "R17") (pin "2") (pinfunction "2_2") (pintype "passive"))
      (node (ref "R9") (pin "2") (pinfunction "2_2") (pintype "passive"))
    )
    (net (code "24") (name "GND") (class "Default")
      (node (ref "C1") (pin "2") (pinfunction "2_2") (pintype "passive"))
      (node (ref "C10") (pin "2") (pinfunction "2_2") (pintype "passive"))
      (node (ref "C11") (pin "2") (pinfunction "2_2") (pintype "passive"))
      (node (ref "C12") (pin "2") (pinfunction "2_2") (pintype "passive"))
      (node (ref "C13") (pin "2") (pinfunction "2_2") (pintype "passive"))
      (node (ref "C14") (pin "2") (pinfunction "2_2") (pintype "passive"))
      (node (ref "C15") (pin "2") (pinfunction "N_2") (pintype "passive"))
      (node (ref "C16") (pin "2") (pinfunction "N_2") (pintype "passive"))
      (node (ref "C17") (pin "2") (pinfunction "N_2") (pintype "passive"))
      (node (ref "C18") (pin "2") (pinfunction "N_2") (pintype "passive"))
      (node (ref "C19") (pin "2") (pinfunction "N_2") (pintype "passive"))
      (node (ref "C2") (pin "2") (pinfunction "2_2") (pintype "passive"))
      (node (ref "C22") (pin "1") (pinfunction "1_1") (pintype "passive"))
      (node (ref "C23") (pin "1") (pinfunction "1_1") (pintype "passive"))
      (node (ref "C24") (pin "1") (pinfunction "1_1") (pintype "passive"))
      (node (ref "C25") (pin "1") (pinfunction "1_1") (pintype "passive"))
      (node (ref "C3") (pin "2") (pinfunction "2_2") (pintype "passive"))
      (node (ref "C4") (pin "2") (pinfunction "2_2") (pintype "passive"))
      (node (ref "C5") (pin "2") (pinfunction "2_2") (pintype "passive"))
      (node (ref "C6") (pin "2") (pinfunction "2_2") (pintype "passive"))
      (node (ref "C7") (pin "2") (pinfunction "2_2") (pintype "passive"))
      (node (ref "C8") (pin "2") (pinfunction "2_2") (pintype "passive"))
      (node (ref "C9") (pin "2") (pinfunction "2_2") (pintype "passive"))
      (node (ref "Q13") (pin "2") (pinfunction "S_2") (pintype "passive"))
      (node (ref "Q14") (pin "2") (pinfunction "S_2") (pintype "passive"))
      (node (ref "Q15") (pin "2") (pinfunction "S_2") (pintype "passive"))
      (node (ref "Q16") (pin "2") (pinfunction "S_2") (pintype "passive"))
      (node (ref "Q5") (pin "2") (pinfunction "S_2") (pintype "passive"))
      (node (ref "Q6") (pin "2") (pinfunction "S_2") (pintype "passive"))
      (node (ref "Q7") (pin "2") (pinfunction "S_2") (pintype "passive"))
      (node (ref "Q8") (pin "2") (pinfunction "S_2") (pintype "passive"))
      (node (ref "R132") (pin "1") (pinfunction "1_1") (pintype "passive"))
      (node (ref "R133") (pin "1") (pinfunction "1_1") (pintype "passive"))
      (node (ref "R134") (pin "1") (pinfunction "1_1") (pintype "passive"))
      (node (ref "R135") (pin "1") (pinfunction "1_1") (pintype "passive"))
    )
    (net (code "25") (name "Net-(D5-A)") (class "Default")
      (node (ref "D5") (pin "1") (pinfunction "A_1") (pintype "passive"))
      (node (ref "Q1") (pin "3") (pinfunction "D_3") (pintype "passive"))
    )
    (net (code "26") (name "Net-(D6-A)") (class "Default")
      (node (ref "D6") (pin "1") (pinfunction "A_1") (pintype "passive"))
      (node (ref "Q2") (pin "3") (pinfunction "D_3") (pintype "passive"))
    )
    (net (code "27") (name "Net-(D7-A)") (class "Default")
      (node (ref "D7") (pin "1") (pinfunction "A_1") (pintype "passive"))
      (node (ref "Q4") (pin "3") (pinfunction "D_3") (pintype "passive"))
    )
    (net (code "28") (name "Net-(D8-A)") (class "Default")
      (node (ref "D8") (pin "1") (pinfunction "A_1") (pintype "passive"))
      (node (ref "Q3") (pin "3") (pinfunction "D_3") (pintype "passive"))
    )
    (net (code "29") (name "Net-(D10-A)") (class "Default")
      (node (ref "D10") (pin "1") (pinfunction "A_1") (pintype "passive"))
      (node (ref "D17") (pin "2") (pinfunction "C_2") (pintype "passive"))
      (node (ref "D9") (pin "1") (pinfunction "A_1") (pintype "passive"))
      (node (ref "Q17") (pin "2") (pinfunction "S_2") (pintype "passive"))
      (node (ref "R25") (pin "1") (pinfunction "1_1") (pintype "passive"))
    )
    (net (code "30") (name "Net-(D11-A)") (class "Default")
      (node (ref "D11") (pin "1") (pinfunction "A_1") (pintype "passive"))
      (node (ref "D18") (pin "2") (pinfunction "C_2") (pintype "passive"))
      (node (ref "Q18") (pin "2") (pinfunction "S_2") (pintype "passive"))
      (node (ref "R25") (pin "2") (pinfunction "2_2") (pintype "passive"))
      (node (ref "R26") (pin "1") (pinfunction "1_1") (pintype "passive"))
    )
    (net (code "31") (name "Net-(D12-A)") (class "Default")
      (node (ref "D12") (pin "1") (pinfunction "A_1") (pintype "passive"))
      (node (ref "D19") (pin "2") (pinfunction "C_2") (pintype "passive"))
      (node (ref "Q19") (pin "2") (pinfunction "S_2") (pintype "passive"))
      (node (ref "R26") (pin "2") (pinfunction "2_2") (pintype "passive"))
      (node (ref "R27") (pin "1") (pinfunction "1_1") (pintype "passive"))
    )
    (net (code "32") (name "Net-(D17-A)") (class "Default")
      (node (ref "D17") (pin "1") (pinfunction "A_1") (pintype "passive"))
      (node (ref "D21") (pin "1") (pinfunction "A_1") (pintype "passive"))
      (node (ref "Q17") (pin "3") (pinfunction "D_3") (pintype "passive"))
      (node (ref "Q21") (pin "3") (pinfunction "D_3") (pintype "passive"))
    )
    (net (code "33") (name "Net-(D18-A)") (class "Default")
      (node (ref "D18") (pin "1") (pinfunction "A_1") (pintype "passive"))
      (node (ref "D22") (pin "1") (pinfunction "A_1") (pintype "passive"))
      (node (ref "Q18") (pin "3") (pinfunction "D_3") (pintype "passive"))
      (node (ref "Q22") (pin "3") (pinfunction "D_3") (pintype "passive"))
    )
    (net (code "34") (name "Net-(D19-A)") (class "Default")
      (node (ref "D19") (pin "1") (pinfunction "A_1") (pintype "passive"))
      (node (ref "D23") (pin "1") (pinfunction "A_1") (pintype "passive"))
      (node (ref "Q19") (pin "3") (pinfunction "D_3") (pintype "passive"))
      (node (ref "Q23") (pin "3") (pinfunction "D_3") (pintype "passive"))
    )
    (net (code "35") (name "Net-(D20-A)") (class "Default")
      (node (ref "D20") (pin "1") (pinfunction "A_1") (pintype "passive"))
      (node (ref "D24") (pin "1") (pinfunction "A_1") (pintype "passive"))
      (node (ref "Q20") (pin "3") (pinfunction "D_3") (pintype "passive"))
      (node (ref "Q24") (pin "3") (pinfunction "D_3") (pintype "passive"))
    )
    (net (code "36") (name "Net-(D20-C)") (class "Default")
      (node (ref "D20") (pin "2") (pinfunction "C_2") (pintype "passive"))
      (node (ref "Q20") (pin "2") (pinfunction "S_2") (pintype "passive"))
      (node (ref "R27") (pin "2") (pinfunction "2_2") (pintype "passive"))
      (node (ref "R28") (pin "1") (pinfunction "1_1") (pintype "passive"))
    )
    (net (code "37") (name "Net-(Q1-G)") (class "Default")
      (node (ref "Q1") (pin "1") (pinfunction "G_1") (pintype "passive"))
      (node (ref "Q5") (pin "3") (pinfunction "D_3") (pintype "passive"))
      (node (ref "R5") (pin "1") (pinfunction "1_1") (pintype "passive"))
    )
    (net (code "38") (name "Net-(Q1-S)") (class "Default")
      (node (ref "Q1") (pin "2") (pinfunction "S_2") (pintype "passive"))
      (node (ref "R1") (pin "1") (pinfunction "1_1") (pintype "passive"))
    )
    (net (code "39") (name "Net-(Q2-G)") (class "Default")
      (node (ref "Q2") (pin "1") (pinfunction "G_1") (pintype "passive"))
      (node (ref "Q6") (pin "3") (pinfunction "D_3") (pintype "passive"))
      (node (ref "R6") (pin "1") (pinfunction "1_1") (pintype "passive"))
    )
    (net (code "40") (name "Net-(Q2-S)") (class "Default")
      (node (ref "Q2") (pin "2") (pinfunction "S_2") (pintype "passive"))
      (node (ref "R2") (pin "1") (pinfunction "1_1") (pintype "passive"))
    )
    (net (code "41") (name "Net-(Q3-G)") (class "Default")
      (node (ref "Q3") (pin "1") (pinfunction "G_1") (pintype "passive"))
      (node (ref "Q7") (pin "3") (pinfunction "D_3") (pintype "passive"))
      (node (ref "R7") (pin "1") (pinfunction "1_1") (pintype "passive"))
    )
    (net (code "42") (name "Net-(Q3-S)") (class "Default")
      (node (ref "Q3") (pin "2") (pinfunction "S_2") (pintype "passive"))
      (node (ref "R3") (pin "1") (pinfunction "1_1") (pintype "passive"))
    )
    (net (code "43") (name "Net-(Q4-G)") (class "Default")
      (node (ref "Q4") (pin "1") (pinfunction "G_1") (pintype "passive"))
      (node (ref "Q8") (pin "3") (pinfunction "D_3") (pintype "passive"))
      (node (ref "R8") (pin "1") (pinfunction "1_1") (pintype "passive"))
    )
    (net (code "44") (name "Net-(Q4-S)") (class "Default")
      (node (ref "Q4") (pin "2") (pinfunction "S_2") (pintype "passive"))
      (node (ref "R4") (pin "1") (pinfunction "1_1") (pintype "passive"))
    )
    (net (code "45") (name "Net-(Q13-D)") (class "Default")
      (node (ref "Q13") (pin "3") (pinfunction "D_3") (pintype "passive"))
      (node (ref "R13") (pin "1") (pinfunction "1_1") (pintype "passive"))
      (node (ref "R21") (pin "2") (pinfunction "2_2") (pintype "passive"))
    )
    (net (code "46") (name "Net-(Q13-G)") (class "Default")
      (node (ref "Q13") (pin "1") (pinfunction "G_1") (pintype "passive"))
      (node (ref "R9") (pin "1") (pinfunction "1_1") (pintype "passive"))
    )
    (net (code "47") (name "Net-(Q14-D)") (class "Default")
      (node (ref "Q14") (pin "3") (pinfunction "D_3") (pintype "passive"))
      (node (ref "R14") (pin "1") (pinfunction "1_1") (pintype "passive"))
      (node (ref "R22") (pin "2") (pinfunction "2_2") (pintype "passive"))
    )
    (net (code "48") (name "Net-(Q14-G)") (class "Default")
      (node (ref "Q14") (pin "1") (pinfunction "G_1") (pintype "passive"))
      (node (ref "R10") (pin "1") (pinfunction "1_1") (pintype "passive"))
    )
    (net (code "49") (name "Net-(Q15-D)") (class "Default")
      (node (ref "Q15") (pin "3") (pinfunction "D_3") (pintype "passive"))
      (node (ref "R15") (pin "1") (pinfunction "1_1") (pintype "passive"))
      (node (ref "R23") (pin "2") (pinfunction "2_2") (pintype "passive"))
    )
    (net (code "50") (name "Net-(Q15-G)") (class "Default")
      (node (ref "Q15") (pin "1") (pinfunction "G_1") (pintype "passive"))
      (node (ref "R11") (pin "1") (pinfunction "1_1") (pintype "passive"))
    )
    (net (code "51") (name "Net-(Q16-D)") (class "Default")
      (node (ref "Q16") (pin "3") (pinfunction "D_3") (pintype "passive"))
      (node (ref "R16") (pin "1") (pinfunction "1_1") (pintype "passive"))
      (node (ref "R24") (pin "2") (pinfunction "2_2") (pintype "passive"))
    )
    (net (code "52") (name "Net-(Q16-G)") (class "Default")
      (node (ref "Q16") (pin "1") (pinfunction "G_1") (pintype "passive"))
      (node (ref "R12") (pin "1") (pinfunction "1_1") (pintype "passive"))
    )
    (net (code "53") (name "VCAP") (class "Default")
      (node (ref "C1") (pin "1") (pinfunction "1_1") (pintype "passive"))
      (node (ref "C2") (pin "1") (pinfunction "1_1") (pintype "passive"))
      (node (ref "R28") (pin "2") (pinfunction "2_2") (pintype "passive"))
      (node (ref "R32") (pin "2") (pinfunction "2_2") (pintype "passive"))
    )
    (net (code "54") (name "VDD_LOAD") (class "Default")
      (node (ref "D1") (pin "1") (pinfunction "A_1") (pintype "passive"))
      (node (ref "D2") (pin "1") (pinfunction "A_1") (pintype "passive"))
      (node (ref "D3") (pin "1") (pinfunction "A_1") (pintype "passive"))
      (node (ref "D4") (pin "1") (pinfunction "A_1") (pintype "passive"))
      (node (ref "Q10") (pin "1") (pinfunction "G_1") (pintype "passive"))
      (node (ref "Q11") (pin "1") (pinfunction "G_1") (pintype "passive"))
      (node (ref "Q12") (pin "1") (pinfunction "G_1") (pintype "passive"))
      (node (ref "Q9") (pin "1") (pinfunction "G_1") (pintype "passive"))
    )
  )
)
